# STM32F103C8T6_MCU.net
KiCad netlist of a schematic drawn in Altium Designer
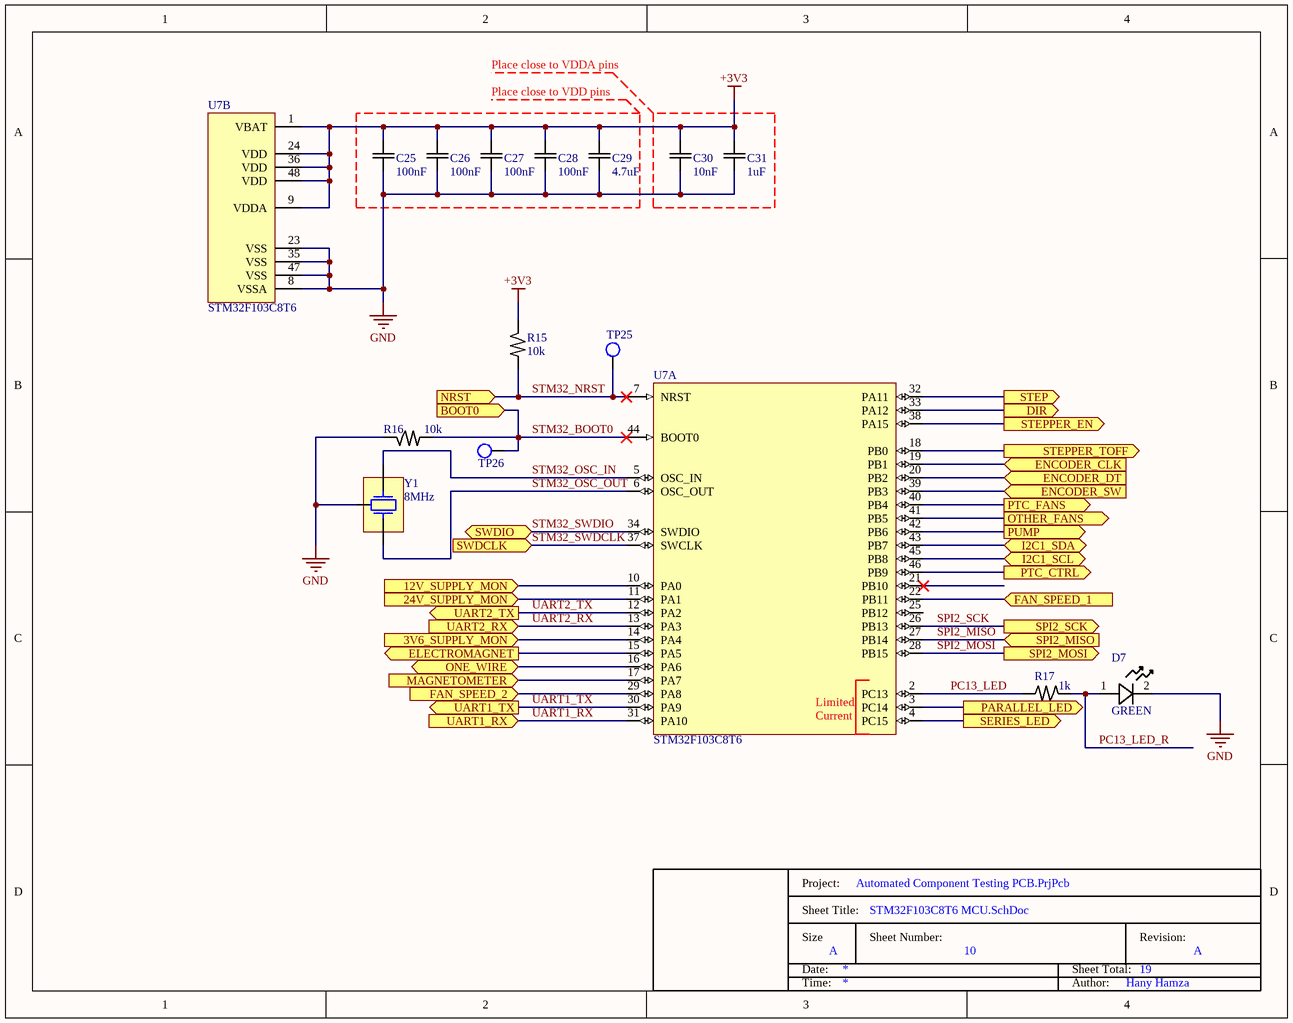
[diagram p0: STM32F103C8T6 MCU.SchDoc]

(export (version "E")
  (design (tool "Eeschema 10.0.6"))
  (components
    (comp (ref "C25")
      (value "100nF")
      (footprint "C0603")
      (description "CAP CER 100nF 50V X7R 0603")
      (fields (field (name "MF") "HRE") (field (name "MP") "CGA0603X7R104K500JT"))
      (libsource (lib "Components") (part "Cap_cer"))
    )
    (comp (ref "C26")
      (value "100nF")
      (footprint "C0603")
      (description "CAP CER 100nF 50V X7R 0603")
      (fields (field (name "MF") "HRE") (field (name "MP") "CGA0603X7R104K500JT"))
      (libsource (lib "Components") (part "Cap_cer"))
    )
    (comp (ref "C27")
      (value "100nF")
      (footprint "C0603")
      (description "CAP CER 100nF 50V X7R 0603")
      (fields (field (name "MF") "HRE") (field (name "MP") "CGA0603X7R104K500JT"))
      (libsource (lib "Components") (part "Cap_cer"))
    )
    (comp (ref "C28")
      (value "100nF")
      (footprint "C0603")
      (description "CAP CER 100nF 50V X7R 0603")
      (fields (field (name "MF") "HRE") (field (name "MP") "CGA0603X7R104K500JT"))
      (libsource (lib "Components") (part "Cap_cer"))
    )
    (comp (ref "C29")
      (value "4.7uF")
      (footprint "C0603")
      (description "10V 4.7uF X7R ±10% 0603 Ceramic Capacitors ROHS")
      (fields (field (name "MF") "Chinocera") (field (name "MP") "HGC0603R7475K100NTHJ"))
      (libsource (lib "Components") (part "Cap_cer"))
    )
    (comp (ref "C30")
      (value "10nF")
      (footprint "C0603")
      (description "CAP CER 10nF 50V X7R 0603")
      (fields (field (name "MF") "HRE") (field (name "MP") "CGA0603X7R103M500JT"))
      (libsource (lib "Components") (part "Cap_cer"))
    )
    (comp (ref "C31")
      (value "1uF")
      (footprint "C0603")
      (description "25V 1uF X7R ±10% 0603 Ceramic Capacitors ROHS")
      (fields (field (name "MF") "Samsung Electro-Mechanics") (field (name "MP") "CL10B105KA8NNNC"))
      (libsource (lib "Components") (part "Cap_cer"))
    )
    (comp (ref "D7")
      (value "GREEN")
      (footprint "LED0805 GREEN")
      (description "LED EMERALD GREEN WATER CLEAR 0805 SMD")
      (fields (field (name "MF") "XINGLIGHT") (field (name "MP") "XL-TD2012UGC"))
      (libsource (lib "Components") (part "LED"))
    )
    (comp (ref "R15")
      (value "10k")
      (footprint "R0603")
      (description "RES 10kΩ ±1% 100mW 0603")
      (fields (field (name "MF") "FOJAN") (field (name "MP") "FRC0603F1002TS"))
      (libsource (lib "Components") (part "Res"))
    )
    (comp (ref "R16")
      (value "10k")
      (footprint "R0603")
      (description "RES 10kΩ ±1% 100mW 0603")
      (fields (field (name "MF") "FOJAN") (field (name "MP") "FRC0603F1002TS"))
      (libsource (lib "Components") (part "Res"))
    )
    (comp (ref "R17")
      (value "1k")
      (footprint "R0603")
      (description "RES 1kΩ ±5% 100mW 0603")
      (fields (field (name "MF") "VO") (field (name "MP") "SCR0603J1K"))
      (libsource (lib "Components") (part "Res"))
    )
    (comp (ref "TP25")
      (value "TestPoint")
      (footprint "TESTPOINT_SMD_1.27MM")
      (libsource (lib "Components") (part "TestPoint"))
    )
    (comp (ref "TP26")
      (value "TestPoint")
      (footprint "TESTPOINT_SMD_1.27MM")
      (libsource (lib "Components") (part "TestPoint"))
    )
    (comp (ref "U7")
      (value "STM32F103C8T6")
      (footprint "STM32-LQFP48")
      (description "ARM-M3 72MHz 128Kb Flash 20Kb SRAM LQFP-48(7x7) Microcontrollers ROHS")
      (fields (field (name "MF") "STMicroelectronics"))
      (libsource (lib "Components") (part "STM32F103C8T6"))
    )
    (comp (ref "Y1")
      (value "8MHz")
      (footprint "Resonator-SMD3213-3P")
      (description "8MHz 10pF 40Ω SMD3213-3P Resonators ROHS")
      (fields (field (name "MF") "muRata") (field (name "MP") "CSTNE8M00G520000R0"))
      (libsource (lib "Components") (part "Resonator"))
    )
  )
  (nets
    (net (code "1") (name "+3V3") (class "Default")
      (node (ref "C25") (pin "2") (pinfunction "2_2") (pintype "passive"))
      (node (ref "C26") (pin "2") (pinfunction "2_2") (pintype "passive"))
      (node (ref "C27") (pin "2") (pinfunction "2_2") (pintype "passive"))
      (node (ref "C28") (pin "2") (pinfunction "2_2") (pintype "passive"))
      (node (ref "C29") (pin "2") (pinfunction "2_2") (pintype "passive"))
      (node (ref "C30") (pin "1") (pinfunction "1_1") (pintype "passive"))
      (node (ref "C31") (pin "1") (pinfunction "1_1") (pintype "passive"))
      (node (ref "R15") (pin "2") (pinfunction "2_2") (pintype "passive"))
      (node (ref "U7") (pin "1") (pinfunction "VBAT_1") (pintype "power_in"))
      (node (ref "U7") (pin "24") (pinfunction "VDD_24") (pintype "power_in"))
      (node (ref "U7") (pin "36") (pinfunction "VDD_36") (pintype "power_in"))
      (node (ref "U7") (pin "48") (pinfunction "VDD_48") (pintype "power_in"))
      (node (ref "U7") (pin "9") (pinfunction "VDDA_9") (pintype "power_in"))
    )
    (net (code "2") (name "/3V6_SUPPLY_MON") (class "Default")
      (node (ref "U7") (pin "14") (pinfunction "PA4_14") (pintype "bidirectional"))
    )
    (net (code "3") (name "/12V_SUPPLY_MON") (class "Default")
      (node (ref "U7") (pin "10") (pinfunction "PA0_10") (pintype "bidirectional"))
    )
    (net (code "4") (name "/24V_SUPPLY_MON") (class "Default")
      (node (ref "U7") (pin "11") (pinfunction "PA1_11") (pintype "bidirectional"))
    )
    (net (code "5") (name "/DIR") (class "Default")
      (node (ref "U7") (pin "33") (pinfunction "PA12_33") (pintype "bidirectional"))
    )
    (net (code "6") (name "/ELECTROMAGNET") (class "Default")
      (node (ref "U7") (pin "15") (pinfunction "PA5_15") (pintype "bidirectional"))
    )
    (net (code "7") (name "/ENCODER_CLK") (class "Default")
      (node (ref "U7") (pin "19") (pinfunction "PB1_19") (pintype "bidirectional"))
    )
    (net (code "8") (name "/ENCODER_DT") (class "Default")
      (node (ref "U7") (pin "20") (pinfunction "PB2_20") (pintype "bidirectional"))
    )
    (net (code "9") (name "/ENCODER_SW") (class "Default")
      (node (ref "U7") (pin "39") (pinfunction "PB3_39") (pintype "bidirectional"))
    )
    (net (code "10") (name "/FAN_SPEED_1") (class "Default")
      (node (ref "U7") (pin "22") (pinfunction "PB11_22") (pintype "bidirectional"))
    )
    (net (code "11") (name "/FAN_SPEED_2") (class "Default")
      (node (ref "U7") (pin "29") (pinfunction "PA8_29") (pintype "bidirectional"))
    )
    (net (code "12") (name "/I2C1_SCL") (class "Default")
      (node (ref "U7") (pin "45") (pinfunction "PB8_45") (pintype "bidirectional"))
    )
    (net (code "13") (name "/I2C1_SDA") (class "Default")
      (node (ref "U7") (pin "43") (pinfunction "PB7_43") (pintype "bidirectional"))
    )
    (net (code "14") (name "/MAGNETOMETER") (class "Default")
      (node (ref "U7") (pin "17") (pinfunction "PA7_17") (pintype "bidirectional"))
    )
    (net (code "15") (name "/ONE_WIRE") (class "Default")
      (node (ref "U7") (pin "16") (pinfunction "PA6_16") (pintype "bidirectional"))
    )
    (net (code "16") (name "/OTHER_FANS") (class "Default")
      (node (ref "U7") (pin "41") (pinfunction "PB5_41") (pintype "bidirectional"))
    )
    (net (code "17") (name "/PARALLEL_LED") (class "Default")
      (node (ref "U7") (pin "3") (pinfunction "PC14_3") (pintype "bidirectional"))
    )
    (net (code "18") (name "/PC13_LED") (class "Default")
      (node (ref "R17") (pin "1") (pinfunction "1_1") (pintype "passive"))
      (node (ref "U7") (pin "2") (pinfunction "PC13_2") (pintype "bidirectional"))
    )
    (net (code "19") (name "/PC13_LED_R") (class "Default")
      (node (ref "D7") (pin "1") (pinfunction "1_1") (pintype "passive"))
      (node (ref "R17") (pin "2") (pinfunction "2_2") (pintype "passive"))
    )
    (net (code "20") (name "/PTC_CTRL") (class "Default")
      (node (ref "U7") (pin "46") (pinfunction "PB9_46") (pintype "bidirectional"))
    )
    (net (code "21") (name "/PTC_FANS") (class "Default")
      (node (ref "U7") (pin "40") (pinfunction "PB4_40") (pintype "bidirectional"))
    )
    (net (code "22") (name "/PUMP") (class "Default")
      (node (ref "U7") (pin "42") (pinfunction "PB6_42") (pintype "bidirectional"))
    )
    (net (code "23") (name "/SERIES_LED") (class "Default")
      (node (ref "U7") (pin "4") (pinfunction "PC15_4") (pintype "bidirectional"))
    )
    (net (code "24") (name "/SPI2_MISO") (class "Default")
      (node (ref "U7") (pin "27") (pinfunction "PB14_27") (pintype "bidirectional"))
    )
    (net (code "25") (name "/SPI2_MOSI") (class "Default")
      (node (ref "U7") (pin "28") (pinfunction "PB15_28") (pintype "bidirectional"))
    )
    (net (code "26") (name "/SPI2_SCK") (class "Default")
      (node (ref "U7") (pin "26") (pinfunction "PB13_26") (pintype "bidirectional"))
    )
    (net (code "27") (name "/STEP") (class "Default")
      (node (ref "U7") (pin "32") (pinfunction "PA11_32") (pintype "bidirectional"))
    )
    (net (code "28") (name "/STEPPER_EN") (class "Default")
      (node (ref "U7") (pin "38") (pinfunction "PA15_38") (pintype "bidirectional"))
    )
    (net (code "29") (name "/STEPPER_TOFF") (class "Default")
      (node (ref "U7") (pin "18") (pinfunction "PB0_18") (pintype "bidirectional"))
    )
    (net (code "30") (name "/STM32_BOOT0") (class "Default")
      (node (ref "R16") (pin "1") (pinfunction "1_1") (pintype "passive"))
      (node (ref "TP26") (pin "1") (pinfunction "1_1") (pintype "passive"))
      (node (ref "U7") (pin "44") (pinfunction "BOOT0_44") (pintype "input"))
    )
    (net (code "31") (name "/STM32_NRST") (class "Default")
      (node (ref "R15") (pin "1") (pinfunction "1_1") (pintype "passive"))
      (node (ref "TP25") (pin "1") (pinfunction "1_1") (pintype "passive"))
      (node (ref "U7") (pin "7") (pinfunction "NRST_7") (pintype "input"))
    )
    (net (code "32") (name "/STM32_OSC_IN") (class "Default")
      (node (ref "U7") (pin "5") (pinfunction "OSC_IN_5") (pintype "bidirectional"))
      (node (ref "Y1") (pin "1") (pintype "passive"))
    )
    (net (code "33") (name "/STM32_OSC_OUT") (class "Default")
      (node (ref "U7") (pin "6") (pinfunction "OSC_OUT_6") (pintype "bidirectional"))
      (node (ref "Y1") (pin "3") (pintype "passive"))
    )
    (net (code "34") (name "/STM32_SWDCLK") (class "Default")
      (node (ref "U7") (pin "37") (pinfunction "SWCLK_37") (pintype "bidirectional"))
    )
    (net (code "35") (name "/STM32_SWDIO") (class "Default")
      (node (ref "U7") (pin "34") (pinfunction "SWDIO_34") (pintype "bidirectional"))
    )
    (net (code "36") (name "/UART1_RX") (class "Default")
      (node (ref "U7") (pin "31") (pinfunction "PA10_31") (pintype "bidirectional"))
    )
    (net (code "37") (name "/UART1_TX") (class "Default")
      (node (ref "U7") (pin "30") (pinfunction "PA9_30") (pintype "bidirectional"))
    )
    (net (code "38") (name "/UART2_RX") (class "Default")
      (node (ref "U7") (pin "13") (pinfunction "PA3_13") (pintype "bidirectional"))
    )
    (net (code "39") (name "/UART2_TX") (class "Default")
      (node (ref "U7") (pin "12") (pinfunction "PA2_12") (pintype "bidirectional"))
    )
    (net (code "40") (name "GND") (class "Default")
      (node (ref "C25") (pin "1") (pinfunction "1_1") (pintype "passive"))
      (node (ref "C26") (pin "1") (pinfunction "1_1") (pintype "passive"))
      (node (ref "C27") (pin "1") (pinfunction "1_1") (pintype "passive"))
      (node (ref "C28") (pin "1") (pinfunction "1_1") (pintype "passive"))
      (node (ref "C29") (pin "1") (pinfunction "1_1") (pintype "passive"))
      (node (ref "C30") (pin "2") (pinfunction "2_2") (pintype "passive"))
      (node (ref "C31") (pin "2") (pinfunction "2_2") (pintype "passive"))
      (node (ref "D7") (pin "2") (pinfunction "2_2") (pintype "passive"))
      (node (ref "R16") (pin "2") (pinfunction "2_2") (pintype "passive"))
      (node (ref "U7") (pin "23") (pinfunction "VSS_23") (pintype "power_in"))
      (node (ref "U7") (pin "35") (pinfunction "VSS_35") (pintype "power_in"))
      (node (ref "U7") (pin "47") (pinfunction "VSS_47") (pintype "power_in"))
      (node (ref "U7") (pin "8") (pinfunction "VSSA_8") (pintype "power_in"))
      (node (ref "Y1") (pin "2") (pintype "passive"))
    )
    (net (code "41") (name "unconnected-(U7A-PB10-Pad21)") (class "Default")
      (node (ref "U7") (pin "21") (pinfunction "PB10_21") (pintype "bidirectional+no_connect"))
    )
    (net (code "42") (name "unconnected-(U7A-PB12-Pad25)") (class "Default")
      (node (ref "U7") (pin "25") (pinfunction "PB12_25") (pintype "bidirectional"))
    )
  )
)
